# acb.net
KiCad netlist of a schematic drawn in EAGLE
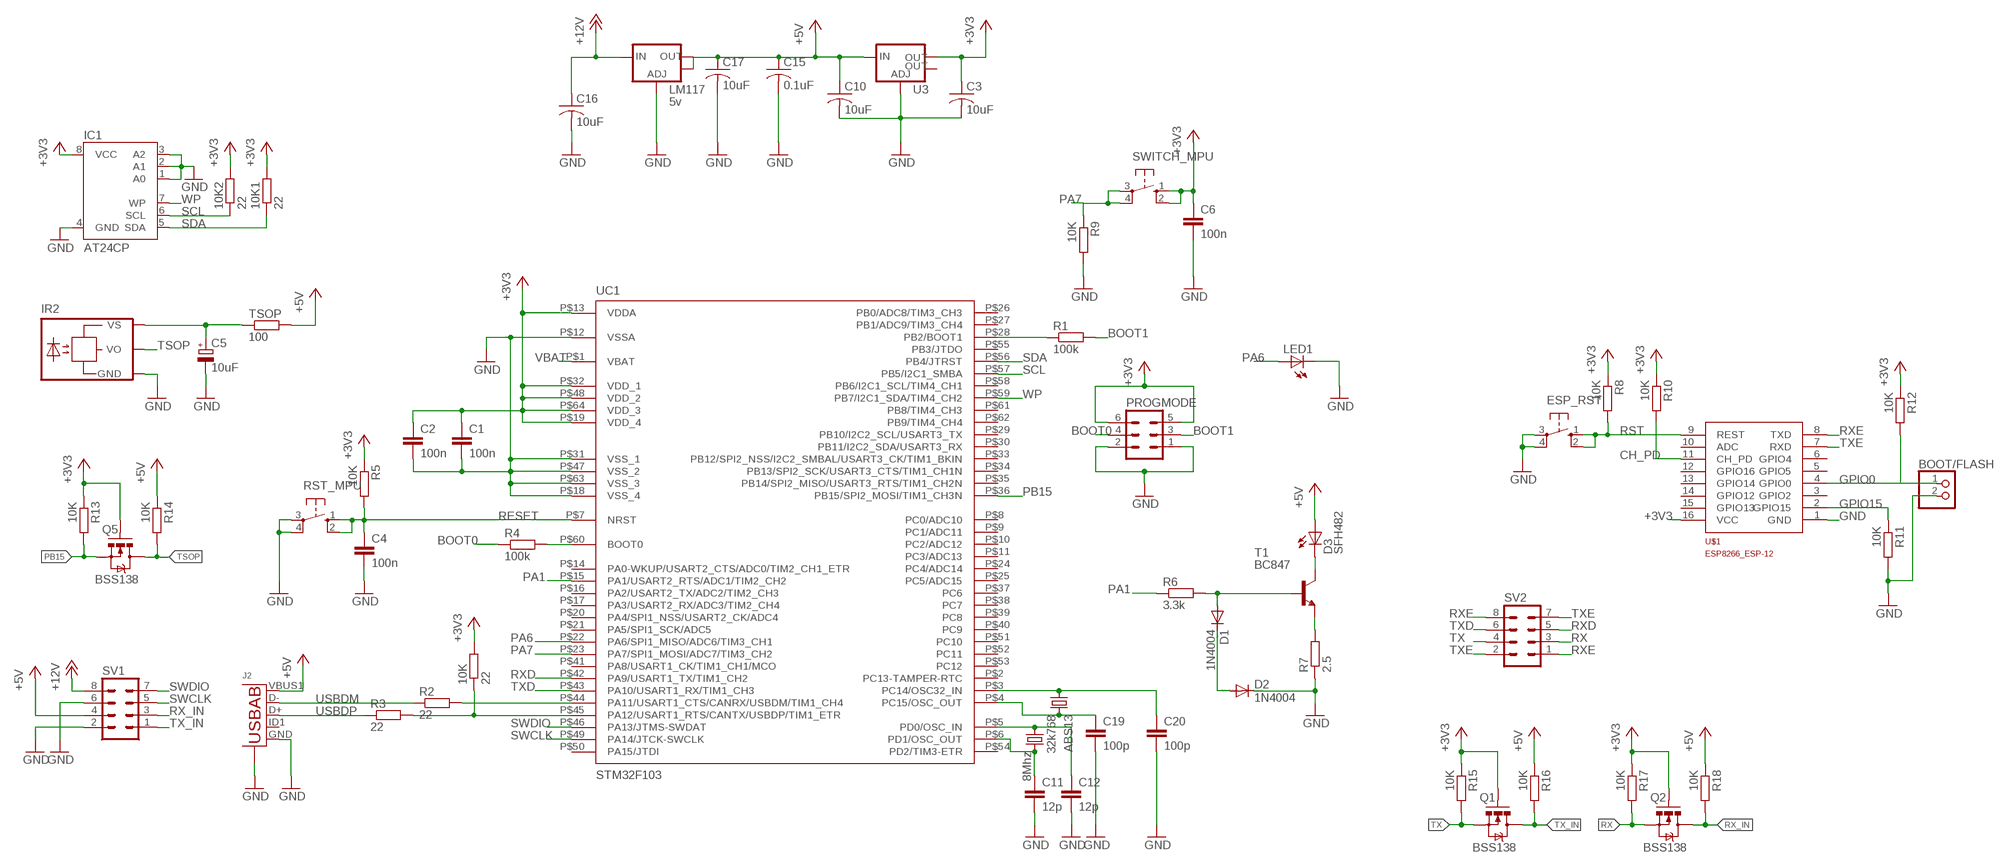
[diagram p0: schematic, sheet 1]

(export (version "E")
  (design (tool "Eeschema 10.0.6"))
  (components
    (comp (ref "10K")
      (value "22")
      (footprint "eagle-import:R1206")
      (libsource (lib "eagle-import") (part "R-EU_R1206"))
    )
    (comp (ref "10K1")
      (value "22")
      (footprint "eagle-import:R1206")
      (libsource (lib "eagle-import") (part "R-EU_R1206"))
    )
    (comp (ref "10K2")
      (value "22")
      (footprint "eagle-import:R1206")
      (libsource (lib "eagle-import") (part "R-EU_R1206"))
    )
    (comp (ref "ABS13")
      (value "32k768")
      (footprint "eagle-import:9HT7")
      (libsource (lib "eagle-import") (part "XTAL_9HT4"))
    )
    (comp (ref "BOOT/FLASH")
      (value "PINHD-1X2")
      (footprint "eagle-import:1X02")
      (libsource (lib "eagle-import") (part "PINHD-1X2"))
    )
    (comp (ref "C1")
      (value "100n")
      (footprint "eagle-import:C1206")
      (libsource (lib "eagle-import") (part "C-EUC1206"))
    )
    (comp (ref "C2")
      (value "100n")
      (footprint "eagle-import:C1206")
      (libsource (lib "eagle-import") (part "C-EUC1206"))
    )
    (comp (ref "C3")
      (value "10uF")
      (footprint "eagle-import:C1206")
      (libsource (lib "eagle-import") (part "C-USC1206"))
    )
    (comp (ref "C4")
      (value "100n")
      (footprint "eagle-import:C1206")
      (libsource (lib "eagle-import") (part "C-EUC1206"))
    )
    (comp (ref "C5")
      (value "10uF")
      (footprint "eagle-import:E2,5-6")
      (libsource (lib "eagle-import") (part "CPOL-EUE2.5-6"))
    )
    (comp (ref "C6")
      (value "100n")
      (footprint "eagle-import:C1206")
      (libsource (lib "eagle-import") (part "C-EUC1206"))
    )
    (comp (ref "C10")
      (value "10uF")
      (footprint "eagle-import:C1206")
      (libsource (lib "eagle-import") (part "C-USC1206"))
    )
    (comp (ref "C11")
      (value "12p")
      (footprint "eagle-import:C1206")
      (libsource (lib "eagle-import") (part "C-EUC1206"))
    )
    (comp (ref "C12")
      (value "12p")
      (footprint "eagle-import:C1206")
      (libsource (lib "eagle-import") (part "C-EUC1206"))
    )
    (comp (ref "C15")
      (value "0.1uF")
      (footprint "eagle-import:C0805")
      (libsource (lib "eagle-import") (part "resistor_C-USC0805"))
    )
    (comp (ref "C16")
      (value "10uF")
      (footprint "eagle-import:C0805")
      (libsource (lib "eagle-import") (part "resistor_C-USC0805"))
    )
    (comp (ref "C17")
      (value "10uF")
      (footprint "eagle-import:C0805")
      (libsource (lib "eagle-import") (part "resistor_C-USC0805"))
    )
    (comp (ref "C19")
      (value "100p")
      (footprint "eagle-import:C1206")
      (libsource (lib "eagle-import") (part "C-EUC1206"))
    )
    (comp (ref "C20")
      (value "100p")
      (footprint "eagle-import:C1206")
      (libsource (lib "eagle-import") (part "C-EUC1206"))
    )
    (comp (ref "D1")
      (value "1N4004")
      (footprint "eagle-import:DO41-10")
      (libsource (lib "eagle-import") (part "1N4004"))
    )
    (comp (ref "D2")
      (value "1N4004")
      (footprint "eagle-import:DO41-10")
      (libsource (lib "eagle-import") (part "1N4004"))
    )
    (comp (ref "D3")
      (value "SFH482")
      (footprint "eagle-import:SFH482")
      (libsource (lib "eagle-import") (part "SFH482"))
    )
    (comp (ref "ESP_RST")
      (value "10-XX")
      (footprint "eagle-import:B3F-10XX")
      (fields (field (name "MPN") "B3F-1000"))
      (libsource (lib "eagle-import") (part "10-XX"))
    )
    (comp (ref "IC1")
      (value "AT24CP")
      (footprint "eagle-import:DIL08")
      (fields (field (name "MPN") "AT24C1024BW-SH-B"))
      (libsource (lib "eagle-import") (part "AT24CP"))
    )
    (comp (ref "IR2")
      (value "TSOP1730TB1")
      (footprint "eagle-import:TSOP17_TB1")
      (libsource (lib "eagle-import") (part "TSOP17TB130"))
    )
    (comp (ref "J2")
      (value "USB-ABBG")
      (footprint "eagle-import:USB-AB-MICRO-SMD_V03_SF")
      (libsource (lib "eagle-import") (part "USB-ABBG"))
    )
    (comp (ref "LED1")
      (value "LED5MM")
      (footprint "eagle-import:LED5MM")
      (libsource (lib "eagle-import") (part "LED5MM"))
    )
    (comp (ref "LM117")
      (value "5v")
      (footprint "eagle-import:SOT223")
      (libsource (lib "eagle-import") (part "V_REG_LM1117SOT223"))
    )
    (comp (ref "PROGMODE")
      (value "MA03-2")
      (footprint "eagle-import:MA03-2")
      (libsource (lib "eagle-import") (part "MA03-2"))
    )
    (comp (ref "Q1")
      (value "BSS138")
      (footprint "eagle-import:SOT23-3")
      (libsource (lib "eagle-import") (part "MOSFET-NCHANNELSMD"))
    )
    (comp (ref "Q2")
      (value "BSS138")
      (footprint "eagle-import:SOT23-3")
      (libsource (lib "eagle-import") (part "MOSFET-NCHANNELSMD"))
    )
    (comp (ref "Q3")
      (value "8Mhz")
      (footprint "eagle-import:HC49U-V")
      (libsource (lib "eagle-import") (part "CRYSTALHC49U-V"))
    )
    (comp (ref "Q5")
      (value "BSS138")
      (footprint "eagle-import:SOT23-3")
      (libsource (lib "eagle-import") (part "MOSFET-NCHANNELSMD"))
    )
    (comp (ref "R1")
      (value "100k")
      (footprint "eagle-import:R1206")
      (libsource (lib "eagle-import") (part "R-EU_R1206"))
    )
    (comp (ref "R2")
      (value "22")
      (footprint "eagle-import:R1206")
      (libsource (lib "eagle-import") (part "R-EU_R1206"))
    )
    (comp (ref "R3")
      (value "22")
      (footprint "eagle-import:R1206")
      (libsource (lib "eagle-import") (part "R-EU_R1206"))
    )
    (comp (ref "R4")
      (value "100k")
      (footprint "eagle-import:R1206")
      (libsource (lib "eagle-import") (part "R-EU_R1206"))
    )
    (comp (ref "R5")
      (value "10K")
      (footprint "eagle-import:R1206")
      (libsource (lib "eagle-import") (part "R-EU_R1206"))
    )
    (comp (ref "R6")
      (value "3.3k")
      (footprint "eagle-import:R1206")
      (libsource (lib "eagle-import") (part "R-EU_R1206"))
    )
    (comp (ref "R7")
      (value "2.5")
      (footprint "eagle-import:R1206")
      (libsource (lib "eagle-import") (part "R-EU_R1206"))
    )
    (comp (ref "R8")
      (value "10K")
      (footprint "eagle-import:R1206")
      (libsource (lib "eagle-import") (part "R-EU_R1206"))
    )
    (comp (ref "R9")
      (value "10K")
      (footprint "eagle-import:R1206")
      (libsource (lib "eagle-import") (part "R-EU_R1206"))
    )
    (comp (ref "R10")
      (value "10K")
      (footprint "eagle-import:R1206")
      (libsource (lib "eagle-import") (part "R-EU_R1206"))
    )
    (comp (ref "R11")
      (value "10K")
      (footprint "eagle-import:R1206")
      (libsource (lib "eagle-import") (part "R-EU_R1206"))
    )
    (comp (ref "R12")
      (value "10K")
      (footprint "eagle-import:R1206")
      (libsource (lib "eagle-import") (part "R-EU_R1206"))
    )
    (comp (ref "R13")
      (value "10K")
      (footprint "eagle-import:R1206")
      (libsource (lib "eagle-import") (part "R-EU_R1206"))
    )
    (comp (ref "R14")
      (value "10K")
      (footprint "eagle-import:R1206")
      (libsource (lib "eagle-import") (part "R-EU_R1206"))
    )
    (comp (ref "R15")
      (value "10K")
      (footprint "eagle-import:R1206")
      (libsource (lib "eagle-import") (part "R-EU_R1206"))
    )
    (comp (ref "R16")
      (value "10K")
      (footprint "eagle-import:R1206")
      (libsource (lib "eagle-import") (part "R-EU_R1206"))
    )
    (comp (ref "R17")
      (value "10K")
      (footprint "eagle-import:R1206")
      (libsource (lib "eagle-import") (part "R-EU_R1206"))
    )
    (comp (ref "R18")
      (value "10K")
      (footprint "eagle-import:R1206")
      (libsource (lib "eagle-import") (part "R-EU_R1206"))
    )
    (comp (ref "RST_MPU")
      (value "10-XX")
      (footprint "eagle-import:B3F-10XX")
      (fields (field (name "MPN") "B3F-1000"))
      (libsource (lib "eagle-import") (part "10-XX"))
    )
    (comp (ref "SV1")
      (value "MA04-2")
      (footprint "eagle-import:MA04-2")
      (libsource (lib "eagle-import") (part "MA04-2"))
    )
    (comp (ref "SV2")
      (value "MA04-2")
      (footprint "eagle-import:MA04-2")
      (libsource (lib "eagle-import") (part "MA04-2"))
    )
    (comp (ref "SWITCH_MPU")
      (value "10-XX")
      (footprint "eagle-import:B3F-10XX")
      (fields (field (name "MPN") "B3F-1000"))
      (libsource (lib "eagle-import") (part "10-XX"))
    )
    (comp (ref "T1")
      (value "BC847")
      (footprint "eagle-import:SOT23")
      (libsource (lib "eagle-import") (part "BC847"))
    )
    (comp (ref "TSOP")
      (value "100")
      (footprint "eagle-import:R1206")
      (libsource (lib "eagle-import") (part "R-EU_R1206"))
    )
    (comp (ref "U$1")
      (value "ESP8266_ESP-12")
      (footprint "eagle-import:ESP8266-ESP12")
      (libsource (lib "eagle-import") (part "ESP8266_ESP-12"))
    )
    (comp (ref "U3")
      (value "V_REG_LM1117SOT223")
      (footprint "eagle-import:SOT223")
      (libsource (lib "eagle-import") (part "SparkFun-PowerIC_V_REG_LM1117SOT223"))
    )
    (comp (ref "UC1")
      (value "STM32F103")
      (footprint "eagle-import:TQFP-10X10-64")
      (libsource (lib "eagle-import") (part "STM32F103"))
    )
  )
  (nets
    (net (code "1") (name "+3V3") (class "Default")
      (node (ref "10K") (pin "2") (pinfunction "2_2") (pintype "passive"))
      (node (ref "10K1") (pin "2") (pinfunction "2_2") (pintype "passive"))
      (node (ref "10K2") (pin "2") (pinfunction "2_2") (pintype "passive"))
      (node (ref "C1") (pin "1") (pinfunction "1_1") (pintype "passive"))
      (node (ref "C2") (pin "1") (pinfunction "1_1") (pintype "passive"))
      (node (ref "C3") (pin "1") (pinfunction "1_1") (pintype "passive"))
      (node (ref "C6") (pin "1") (pinfunction "1_1") (pintype "passive"))
      (node (ref "IC1") (pin "8") (pinfunction "VCC_8") (pintype "power_in"))
      (node (ref "PROGMODE") (pin "5") (pinfunction "5_5") (pintype "passive"))
      (node (ref "PROGMODE") (pin "6") (pinfunction "6_6") (pintype "passive"))
      (node (ref "Q1") (pin "1") (pinfunction "G_1") (pintype "passive"))
      (node (ref "Q2") (pin "1") (pinfunction "G_1") (pintype "passive"))
      (node (ref "Q5") (pin "1") (pinfunction "G_1") (pintype "passive"))
      (node (ref "R10") (pin "1") (pinfunction "1_1") (pintype "passive"))
      (node (ref "R12") (pin "1") (pinfunction "1_1") (pintype "passive"))
      (node (ref "R13") (pin "1") (pinfunction "1_1") (pintype "passive"))
      (node (ref "R15") (pin "1") (pinfunction "1_1") (pintype "passive"))
      (node (ref "R17") (pin "1") (pinfunction "1_1") (pintype "passive"))
      (node (ref "R5") (pin "1") (pinfunction "1_1") (pintype "passive"))
      (node (ref "R8") (pin "1") (pinfunction "1_1") (pintype "passive"))
      (node (ref "SWITCH_MPU") (pin "1") (pinfunction "S_1") (pintype "passive"))
      (node (ref "SWITCH_MPU") (pin "2") (pinfunction "S1_2") (pintype "passive"))
      (node (ref "U$1") (pin "16") (pinfunction "VCC_16") (pintype "bidirectional"))
      (node (ref "U3") (pin "2") (pinfunction "OUT_2") (pintype "output"))
      (node (ref "UC1") (pin "P$13") (pinfunction "VDDA_P$13") (pintype "power_in"))
      (node (ref "UC1") (pin "P$19") (pinfunction "VDD_4_P$19") (pintype "power_in"))
      (node (ref "UC1") (pin "P$32") (pinfunction "VDD_1_P$32") (pintype "power_in"))
      (node (ref "UC1") (pin "P$48") (pinfunction "VDD_2_P$48") (pintype "power_in"))
      (node (ref "UC1") (pin "P$64") (pinfunction "VDD_3_P$64") (pintype "power_in"))
    )
    (net (code "2") (name "+5V") (class "Default")
      (node (ref "C10") (pin "1") (pinfunction "1_1") (pintype "passive"))
      (node (ref "C15") (pin "1") (pinfunction "1_1") (pintype "passive"))
      (node (ref "C17") (pin "1") (pinfunction "1_1") (pintype "passive"))
      (node (ref "D3") (pin "A") (pinfunction "A_A") (pintype "passive"))
      (node (ref "J2") (pin "VBUS1") (pinfunction "VBUS_VBUS1") (pintype "bidirectional"))
      (node (ref "LM117") (pin "2") (pinfunction "OUT_2") (pintype "output"))
      (node (ref "LM117") (pin "4") (pinfunction "OUT_4") (pintype "output"))
      (node (ref "R14") (pin "1") (pinfunction "1_1") (pintype "passive"))
      (node (ref "R16") (pin "1") (pinfunction "1_1") (pintype "passive"))
      (node (ref "R18") (pin "1") (pinfunction "1_1") (pintype "passive"))
      (node (ref "SV1") (pin "4") (pinfunction "4_4") (pintype "passive"))
      (node (ref "TSOP") (pin "2") (pinfunction "2_2") (pintype "passive"))
      (node (ref "U3") (pin "3") (pinfunction "IN_3") (pintype "input"))
    )
    (net (code "3") (name "+12V") (class "Default")
      (node (ref "C16") (pin "1") (pinfunction "1_1") (pintype "passive"))
      (node (ref "LM117") (pin "3") (pinfunction "IN_3") (pintype "input"))
      (node (ref "SV1") (pin "8") (pinfunction "8_8") (pintype "passive"))
    )
    (net (code "4") (name "/BOOT0") (class "Default")
      (node (ref "PROGMODE") (pin "4") (pinfunction "4_4") (pintype "passive"))
      (node (ref "R4") (pin "1") (pinfunction "1_1") (pintype "passive"))
    )
    (net (code "5") (name "/BOOT1") (class "Default")
      (node (ref "PROGMODE") (pin "3") (pinfunction "3_3") (pintype "passive"))
      (node (ref "R1") (pin "2") (pinfunction "2_2") (pintype "passive"))
    )
    (net (code "6") (name "/CH_PD") (class "Default")
      (node (ref "R10") (pin "2") (pinfunction "2_2") (pintype "passive"))
      (node (ref "U$1") (pin "11") (pinfunction "CH_PD_11") (pintype "bidirectional"))
    )
    (net (code "7") (name "/GPIO0") (class "Default")
      (node (ref "BOOT/FLASH") (pin "1") (pinfunction "1_1") (pintype "passive"))
      (node (ref "R12") (pin "2") (pinfunction "2_2") (pintype "passive"))
      (node (ref "U$1") (pin "4") (pinfunction "GPIO0_4") (pintype "bidirectional"))
    )
    (net (code "8") (name "/GPIO15") (class "Default")
      (node (ref "R11") (pin "1") (pinfunction "1_1") (pintype "passive"))
      (node (ref "U$1") (pin "2") (pinfunction "GPIO15_2") (pintype "bidirectional"))
    )
    (net (code "9") (name "/PA1") (class "Default")
      (node (ref "R6") (pin "1") (pinfunction "1_1") (pintype "passive"))
      (node (ref "UC1") (pin "P$15") (pinfunction "PA1/USART2_RTS/ADC1/TIM2_CH2_P$15") (pintype "bidirectional"))
    )
    (net (code "10") (name "/PA6") (class "Default")
      (node (ref "LED1") (pin "A") (pinfunction "A_A") (pintype "passive"))
      (node (ref "UC1") (pin "P$22") (pinfunction "PA6/SPI1_MISO/ADC6/TIM3_CH1_P$22") (pintype "bidirectional"))
    )
    (net (code "11") (name "/PA7") (class "Default")
      (node (ref "R9") (pin "1") (pinfunction "1_1") (pintype "passive"))
      (node (ref "SWITCH_MPU") (pin "3") (pinfunction "P_3") (pintype "passive"))
      (node (ref "SWITCH_MPU") (pin "4") (pinfunction "P1_4") (pintype "passive"))
      (node (ref "UC1") (pin "P$23") (pinfunction "PA7/SPI1_MOSI/ADC7/TIM3_CH2_P$23") (pintype "bidirectional"))
    )
    (net (code "12") (name "/RESET") (class "Default")
      (node (ref "C4") (pin "1") (pinfunction "1_1") (pintype "passive"))
      (node (ref "R5") (pin "2") (pinfunction "2_2") (pintype "passive"))
      (node (ref "RST_MPU") (pin "1") (pinfunction "S_1") (pintype "passive"))
      (node (ref "RST_MPU") (pin "2") (pinfunction "S1_2") (pintype "passive"))
      (node (ref "UC1") (pin "P$7") (pinfunction "NRST_P$7") (pintype "bidirectional"))
    )
    (net (code "13") (name "/RST") (class "Default")
      (node (ref "ESP_RST") (pin "1") (pinfunction "S_1") (pintype "passive"))
      (node (ref "ESP_RST") (pin "2") (pinfunction "S1_2") (pintype "passive"))
      (node (ref "R8") (pin "2") (pinfunction "2_2") (pintype "passive"))
      (node (ref "U$1") (pin "9") (pinfunction "REST_9") (pintype "bidirectional"))
    )
    (net (code "14") (name "/RXD") (class "Default")
      (node (ref "SV2") (pin "5") (pinfunction "5_5") (pintype "passive"))
      (node (ref "UC1") (pin "P$42") (pinfunction "PA9/USART1_TX/TIM1_CH2_P$42") (pintype "bidirectional"))
    )
    (net (code "15") (name "/RXE") (class "Default")
      (node (ref "SV2") (pin "1") (pinfunction "1_1") (pintype "passive"))
      (node (ref "SV2") (pin "8") (pinfunction "8_8") (pintype "passive"))
      (node (ref "U$1") (pin "8") (pinfunction "TXD_8") (pintype "bidirectional"))
    )
    (net (code "16") (name "/SCL") (class "Default")
      (node (ref "10K2") (pin "1") (pinfunction "1_1") (pintype "passive"))
      (node (ref "IC1") (pin "6") (pinfunction "SCL_6") (pintype "bidirectional"))
      (node (ref "UC1") (pin "P$57") (pinfunction "PB5/I2C1_SMBA_P$57") (pintype "bidirectional"))
    )
    (net (code "17") (name "/SDA") (class "Default")
      (node (ref "10K1") (pin "1") (pinfunction "1_1") (pintype "passive"))
      (node (ref "IC1") (pin "5") (pinfunction "SDA_5") (pintype "bidirectional"))
      (node (ref "UC1") (pin "P$56") (pinfunction "PB4/JTRST_P$56") (pintype "bidirectional"))
    )
    (net (code "18") (name "/SWCLK") (class "Default")
      (node (ref "SV1") (pin "5") (pinfunction "5_5") (pintype "passive"))
      (node (ref "UC1") (pin "P$49") (pinfunction "PA14/JTCK-SWCLK_P$49") (pintype "bidirectional"))
    )
    (net (code "19") (name "/SWDIO") (class "Default")
      (node (ref "SV1") (pin "7") (pinfunction "7_7") (pintype "passive"))
      (node (ref "UC1") (pin "P$46") (pinfunction "PA13/JTMS-SWDAT_P$46") (pintype "bidirectional"))
    )
    (net (code "20") (name "/TXD") (class "Default")
      (node (ref "SV2") (pin "6") (pinfunction "6_6") (pintype "passive"))
      (node (ref "UC1") (pin "P$43") (pinfunction "PA10/USART1_RX/TIM1_CH3_P$43") (pintype "bidirectional"))
    )
    (net (code "21") (name "/TXE") (class "Default")
      (node (ref "SV2") (pin "2") (pinfunction "2_2") (pintype "passive"))
      (node (ref "SV2") (pin "7") (pinfunction "7_7") (pintype "passive"))
      (node (ref "U$1") (pin "7") (pinfunction "RXD_7") (pintype "bidirectional"))
    )
    (net (code "22") (name "/USBDM") (class "Default")
      (node (ref "J2") (pin "D-") (pinfunction "D-_D-") (pintype "bidirectional"))
      (node (ref "R2") (pin "1") (pinfunction "1_1") (pintype "passive"))
    )
    (net (code "23") (name "/USBDP") (class "Default")
      (node (ref "J2") (pin "D+") (pinfunction "D+_D+") (pintype "bidirectional"))
      (node (ref "R3") (pin "1") (pinfunction "1_1") (pintype "passive"))
    )
    (net (code "24") (name "/VBAT") (class "Default")
      (node (ref "UC1") (pin "P$1") (pinfunction "VBAT_P$1") (pintype "power_in"))
    )
    (net (code "25") (name "/WP") (class "Default")
      (node (ref "IC1") (pin "7") (pinfunction "WP_7") (pintype "input"))
      (node (ref "UC1") (pin "P$59") (pinfunction "PB7/I2C1_SDA/TIM4_CH2_P$59") (pintype "bidirectional"))
    )
    (net (code "26") (name "GND") (class "Default")
      (node (ref "BOOT/FLASH") (pin "2") (pinfunction "2_2") (pintype "passive"))
      (node (ref "C1") (pin "2") (pinfunction "2_2") (pintype "passive"))
      (node (ref "C10") (pin "2") (pinfunction "2_2") (pintype "passive"))
      (node (ref "C11") (pin "2") (pinfunction "2_2") (pintype "passive"))
      (node (ref "C12") (pin "2") (pinfunction "2_2") (pintype "passive"))
      (node (ref "C15") (pin "2") (pinfunction "2_2") (pintype "passive"))
      (node (ref "C16") (pin "2") (pinfunction "2_2") (pintype "passive"))
      (node (ref "C17") (pin "2") (pinfunction "2_2") (pintype "passive"))
      (node (ref "C19") (pin "2") (pinfunction "2_2") (pintype "passive"))
      (node (ref "C2") (pin "2") (pinfunction "2_2") (pintype "passive"))
      (node (ref "C20") (pin "2") (pinfunction "2_2") (pintype "passive"))
      (node (ref "C3") (pin "2") (pinfunction "2_2") (pintype "passive"))
      (node (ref "C4") (pin "2") (pinfunction "2_2") (pintype "passive"))
      (node (ref "C5") (pin "-") (pinfunction "-_-") (pintype "passive"))
      (node (ref "C6") (pin "2") (pinfunction "2_2") (pintype "passive"))
      (node (ref "D2") (pin "C") (pinfunction "C_C") (pintype "passive"))
      (node (ref "ESP_RST") (pin "3") (pinfunction "P_3") (pintype "passive"))
      (node (ref "ESP_RST") (pin "4") (pinfunction "P1_4") (pintype "passive"))
      (node (ref "IC1") (pin "1") (pinfunction "A0_1") (pintype "input"))
      (node (ref "IC1") (pin "2") (pinfunction "A1_2") (pintype "input"))
      (node (ref "IC1") (pin "3") (pinfunction "A2_3") (pintype "input"))
      (node (ref "IC1") (pin "4") (pinfunction "GND_4") (pintype "power_in"))
      (node (ref "IR2") (pin "GND") (pinfunction "GND_GND") (pintype "power_in"))
      (node (ref "J2") (pin "GND") (pinfunction "GND_GND") (pintype "bidirectional"))
      (node (ref "J2") (pin "S1") (pinfunction "S_S1") (pintype "bidirectional"))
      (node (ref "J2") (pin "S2") (pinfunction "S_S2") (pintype "bidirectional"))
      (node (ref "J2") (pin "S3") (pinfunction "S_S3") (pintype "bidirectional"))
      (node (ref "J2") (pin "S4") (pinfunction "S_S4") (pintype "bidirectional"))
      (node (ref "LED1") (pin "K") (pinfunction "C_K") (pintype "passive"))
      (node (ref "LM117") (pin "1") (pinfunction "ADJ_1") (pintype "input"))
      (node (ref "PROGMODE") (pin "1") (pinfunction "1_1") (pintype "passive"))
      (node (ref "PROGMODE") (pin "2") (pinfunction "2_2") (pintype "passive"))
      (node (ref "R11") (pin "2") (pinfunction "2_2") (pintype "passive"))
      (node (ref "R7") (pin "1") (pinfunction "1_1") (pintype "passive"))
      (node (ref "R9") (pin "2") (pinfunction "2_2") (pintype "passive"))
      (node (ref "RST_MPU") (pin "3") (pinfunction "P_3") (pintype "passive"))
      (node (ref "RST_MPU") (pin "4") (pinfunction "P1_4") (pintype "passive"))
      (node (ref "SV1") (pin "2") (pinfunction "2_2") (pintype "passive"))
      (node (ref "SV1") (pin "6") (pinfunction "6_6") (pintype "passive"))
      (node (ref "U$1") (pin "1") (pinfunction "GND_1") (pintype "bidirectional"))
      (node (ref "U3") (pin "1") (pinfunction "ADJ_1") (pintype "input"))
      (node (ref "UC1") (pin "P$12") (pinfunction "VSSA_P$12") (pintype "power_in"))
      (node (ref "UC1") (pin "P$18") (pinfunction "VSS_4_P$18") (pintype "power_in"))
      (node (ref "UC1") (pin "P$31") (pinfunction "VSS_1_P$31") (pintype "power_in"))
      (node (ref "UC1") (pin "P$47") (pinfunction "VSS_2_P$47") (pintype "power_in"))
      (node (ref "UC1") (pin "P$63") (pinfunction "VSS_3_P$63") (pintype "power_in"))
    )
    (net (code "27") (name "Net-(ABS13-2)") (class "Default")
      (node (ref "ABS13") (pin "4") (pinfunction "2_4") (pintype "passive"))
      (node (ref "C19") (pin "1") (pinfunction "1_1") (pintype "passive"))
      (node (ref "UC1") (pin "P$4") (pinfunction "PC15/OSC_OUT_P$4") (pintype "bidirectional"))
    )
    (net (code "28") (name "Net-(C5-Pad+)") (class "Default")
      (node (ref "C5") (pin "+") (pinfunction "+_+") (pintype "passive"))
      (node (ref "IR2") (pin "VS") (pinfunction "VS_VS") (pintype "power_in"))
      (node (ref "TSOP") (pin "1") (pinfunction "1_1") (pintype "passive"))
    )
    (net (code "29") (name "Net-(D1-PadC)") (class "Default")
      (node (ref "D1") (pin "C") (pinfunction "C_C") (pintype "passive"))
      (node (ref "D2") (pin "A") (pinfunction "A_A") (pintype "passive"))
    )
    (net (code "30") (name "Net-(D3-C)") (class "Default")
      (node (ref "D3") (pin "K") (pinfunction "C_K") (pintype "passive"))
      (node (ref "T1") (pin "3") (pinfunction "C_3") (pintype "passive"))
    )
    (net (code "31") (name "Net-(T1-B)") (class "Default")
      (node (ref "D1") (pin "A") (pinfunction "A_A") (pintype "passive"))
      (node (ref "R6") (pin "2") (pinfunction "2_2") (pintype "passive"))
      (node (ref "T1") (pin "1") (pinfunction "B_1") (pintype "passive"))
    )
    (net (code "32") (name "Net-(T1-E)") (class "Default")
      (node (ref "R7") (pin "2") (pinfunction "2_2") (pintype "passive"))
      (node (ref "T1") (pin "2") (pinfunction "E_2") (pintype "passive"))
    )
    (net (code "33") (name "Net-(UC1-BOOT0)") (class "Default")
      (node (ref "R4") (pin "2") (pinfunction "2_2") (pintype "passive"))
      (node (ref "UC1") (pin "P$60") (pinfunction "BOOT0_P$60") (pintype "bidirectional"))
    )
    (net (code "34") (name "Net-(UC1-PA11{slash}USART1_CTS{slash}CANRX{slash}USBDM{slash}TIM1_CH4)") (class "Default")
      (node (ref "R2") (pin "2") (pinfunction "2_2") (pintype "passive"))
      (node (ref "UC1") (pin "P$44") (pinfunction "PA11/USART1_CTS/CANRX/USBDM/TIM1_CH4_P$44") (pintype "bidirectional"))
    )
    (net (code "35") (name "Net-(UC1-PA12{slash}USART1_RTS{slash}CANTX{slash}USBDP{slash}TIM1_ETR)") (class "Default")
      (node (ref "10K") (pin "1") (pinfunction "1_1") (pintype "passive"))
      (node (ref "R3") (pin "2") (pinfunction "2_2") (pintype "passive"))
      (node (ref "UC1") (pin "P$45") (pinfunction "PA12/USART1_RTS/CANTX/USBDP/TIM1_ETR_P$45") (pintype "bidirectional"))
    )
    (net (code "36") (name "Net-(UC1-PB2{slash}BOOT1)") (class "Default")
      (node (ref "R1") (pin "1") (pinfunction "1_1") (pintype "passive"))
      (node (ref "UC1") (pin "P$28") (pinfunction "PB2/BOOT1_P$28") (pintype "bidirectional"))
    )
    (net (code "37") (name "Net-(UC1-PC14{slash}OSC32_IN)") (class "Default")
      (node (ref "ABS13") (pin "1") (pinfunction "1_1") (pintype "passive"))
      (node (ref "C20") (pin "1") (pinfunction "1_1") (pintype "passive"))
      (node (ref "UC1") (pin "P$3") (pinfunction "PC14/OSC32_IN_P$3") (pintype "bidirectional"))
    )
    (net (code "38") (name "Net-(UC1-PD0{slash}OSC_IN)") (class "Default")
      (node (ref "C12") (pin "1") (pinfunction "1_1") (pintype "passive"))
      (node (ref "Q3") (pin "1") (pinfunction "1_1") (pintype "passive"))
      (node (ref "UC1") (pin "P$5") (pinfunction "PD0/OSC_IN_P$5") (pintype "bidirectional"))
    )
    (net (code "39") (name "Net-(UC1-PD1{slash}OSC_OUT)") (class "Default")
      (node (ref "C11") (pin "1") (pinfunction "1_1") (pintype "passive"))
      (node (ref "Q3") (pin "2") (pinfunction "2_2") (pintype "passive"))
      (node (ref "UC1") (pin "P$6") (pinfunction "PD1/OSC_OUT_P$6") (pintype "bidirectional"))
    )
    (net (code "40") (name "PB15") (class "Default")
      (node (ref "Q5") (pin "2") (pinfunction "S_2") (pintype "passive"))
      (node (ref "R13") (pin "2") (pinfunction "2_2") (pintype "passive"))
      (node (ref "UC1") (pin "P$36") (pinfunction "PB15/SPI2_MOSI/TIM1_CH3N_P$36") (pintype "bidirectional"))
    )
    (net (code "41") (name "RX") (class "Default")
      (node (ref "Q2") (pin "2") (pinfunction "S_2") (pintype "passive"))
      (node (ref "R17") (pin "2") (pinfunction "2_2") (pintype "passive"))
      (node (ref "SV2") (pin "3") (pinfunction "3_3") (pintype "passive"))
    )
    (net (code "42") (name "RX_IN") (class "Default")
      (node (ref "Q2") (pin "3") (pinfunction "D_3") (pintype "passive"))
      (node (ref "R18") (pin "2") (pinfunction "2_2") (pintype "passive"))
      (node (ref "SV1") (pin "3") (pinfunction "3_3") (pintype "passive"))
    )
    (net (code "43") (name "TSOP") (class "Default")
      (node (ref "IR2") (pin "VO") (pinfunction "VO_VO") (pintype "open_collector"))
      (node (ref "Q5") (pin "3") (pinfunction "D_3") (pintype "passive"))
      (node (ref "R14") (pin "2") (pinfunction "2_2") (pintype "passive"))
    )
    (net (code "44") (name "TX") (class "Default")
      (node (ref "Q1") (pin "2") (pinfunction "S_2") (pintype "passive"))
      (node (ref "R15") (pin "2") (pinfunction "2_2") (pintype "passive"))
      (node (ref "SV2") (pin "4") (pinfunction "4_4") (pintype "passive"))
    )
    (net (code "45") (name "TX_IN") (class "Default")
      (node (ref "Q1") (pin "3") (pinfunction "D_3") (pintype "passive"))
      (node (ref "R16") (pin "2") (pinfunction "2_2") (pintype "passive"))
      (node (ref "SV1") (pin "1") (pinfunction "1_1") (pintype "passive"))
    )
    (net (code "46") (name "unconnected-(J2-USBID-PadID1)") (class "Default")
      (node (ref "J2") (pin "ID1") (pinfunction "USBID_ID1") (pintype "bidirectional"))
    )
    (net (code "47") (name "unconnected-(U$1-ADC-Pad10)") (class "Default")
      (node (ref "U$1") (pin "10") (pinfunction "ADC_10") (pintype "bidirectional"))
    )
    (net (code "48") (name "unconnected-(U$1-GPIO2-Pad3)") (class "Default")
      (node (ref "U$1") (pin "3") (pinfunction "GPIO2_3") (pintype "bidirectional"))
    )
    (net (code "49") (name "unconnected-(U$1-GPIO4-Pad6)") (class "Default")
      (node (ref "U$1") (pin "6") (pinfunction "GPIO4_6") (pintype "bidirectional"))
    )
    (net (code "50") (name "unconnected-(U$1-GPIO5-Pad5)") (class "Default")
      (node (ref "U$1") (pin "5") (pinfunction "GPIO5_5") (pintype "bidirectional"))
    )
    (net (code "51") (name "unconnected-(U$1-GPIO12-Pad14)") (class "Default")
      (node (ref "U$1") (pin "14") (pinfunction "GPIO12_14") (pintype "bidirectional"))
    )
    (net (code "52") (name "unconnected-(U$1-GPIO13-Pad15)") (class "Default")
      (node (ref "U$1") (pin "15") (pinfunction "GPIO13_15") (pintype "bidirectional"))
    )
    (net (code "53") (name "unconnected-(U$1-GPIO14-Pad13)") (class "Default")
      (node (ref "U$1") (pin "13") (pinfunction "GPIO14_13") (pintype "bidirectional"))
    )
    (net (code "54") (name "unconnected-(U$1-GPIO16-Pad12)") (class "Default")
      (node (ref "U$1") (pin "12") (pinfunction "GPIO16_12") (pintype "bidirectional"))
    )
    (net (code "55") (name "unconnected-(U3-OUT-Pad4)") (class "Default")
      (node (ref "U3") (pin "4") (pinfunction "OUT_4") (pintype "output"))
    )
    (net (code "56") (name "unconnected-(UC1-PA0-WKUP{slash}USART2_CTS{slash}ADC0{slash}TIM2_CH1_ETR-PadP$14)") (class "Default")
      (node (ref "UC1") (pin "P$14") (pinfunction "PA0-WKUP/USART2_CTS/ADC0/TIM2_CH1_ETR_P$14") (pintype "bidirectional"))
    )
    (net (code "57") (name "unconnected-(UC1-PA2{slash}USART2_TX{slash}ADC2{slash}TIM2_CH3-PadP$16)") (class "Default")
      (node (ref "UC1") (pin "P$16") (pinfunction "PA2/USART2_TX/ADC2/TIM2_CH3_P$16") (pintype "bidirectional"))
    )
    (net (code "58") (name "unconnected-(UC1-PA3{slash}USART2_RX{slash}ADC3{slash}TIM2_CH4-PadP$17)") (class "Default")
      (node (ref "UC1") (pin "P$17") (pinfunction "PA3/USART2_RX/ADC3/TIM2_CH4_P$17") (pintype "bidirectional"))
    )
    (net (code "59") (name "unconnected-(UC1-PA4{slash}SPI1_NSS{slash}USART2_CK{slash}ADC4-PadP$20)") (class "Default")
      (node (ref "UC1") (pin "P$20") (pinfunction "PA4/SPI1_NSS/USART2_CK/ADC4_P$20") (pintype "bidirectional"))
    )
    (net (code "60") (name "unconnected-(UC1-PA5{slash}SPI1_SCK{slash}ADC5-PadP$21)") (class "Default")
      (node (ref "UC1") (pin "P$21") (pinfunction "PA5/SPI1_SCK/ADC5_P$21") (pintype "bidirectional"))
    )
    (net (code "61") (name "unconnected-(UC1-PA8{slash}USART1_CK{slash}TIM1_CH1{slash}MCO-PadP$41)") (class "Default")
      (node (ref "UC1") (pin "P$41") (pinfunction "PA8/USART1_CK/TIM1_CH1/MCO_P$41") (pintype "bidirectional"))
    )
    (net (code "62") (name "unconnected-(UC1-PA15{slash}JTDI-PadP$50)") (class "Default")
      (node (ref "UC1") (pin "P$50") (pinfunction "PA15/JTDI_P$50") (pintype "bidirectional"))
    )
    (net (code "63") (name "unconnected-(UC1-PB0{slash}ADC8{slash}TIM3_CH3-PadP$26)") (class "Default")
      (node (ref "UC1") (pin "P$26") (pinfunction "PB0/ADC8/TIM3_CH3_P$26") (pintype "bidirectional"))
    )
    (net (code "64") (name "unconnected-(UC1-PB1{slash}ADC9{slash}TIM3_CH4-PadP$27)") (class "Default")
      (node (ref "UC1") (pin "P$27") (pinfunction "PB1/ADC9/TIM3_CH4_P$27") (pintype "bidirectional"))
    )
    (net (code "65") (name "unconnected-(UC1-PB3{slash}JTDO-PadP$55)") (class "Default")
      (node (ref "UC1") (pin "P$55") (pinfunction "PB3/JTDO_P$55") (pintype "bidirectional"))
    )
    (net (code "66") (name "unconnected-(UC1-PB6{slash}I2C1_SCL{slash}TIM4_CH1-PadP$58)") (class "Default")
      (node (ref "UC1") (pin "P$58") (pinfunction "PB6/I2C1_SCL/TIM4_CH1_P$58") (pintype "bidirectional"))
    )
    (net (code "67") (name "unconnected-(UC1-PB8{slash}TIM4_CH3-PadP$61)") (class "Default")
      (node (ref "UC1") (pin "P$61") (pinfunction "PB8/TIM4_CH3_P$61") (pintype "bidirectional"))
    )
    (net (code "68") (name "unconnected-(UC1-PB9{slash}TIM4_CH4-PadP$62)") (class "Default")
      (node (ref "UC1") (pin "P$62") (pinfunction "PB9/TIM4_CH4_P$62") (pintype "bidirectional"))
    )
    (net (code "69") (name "unconnected-(UC1-PB10{slash}I2C2_SCL{slash}USART3_TX-PadP$29)") (class "Default")
      (node (ref "UC1") (pin "P$29") (pinfunction "PB10/I2C2_SCL/USART3_TX_P$29") (pintype "bidirectional"))
    )
    (net (code "70") (name "unconnected-(UC1-PB11{slash}I2C2_SDA{slash}USART3_RX-PadP$30)") (class "Default")
      (node (ref "UC1") (pin "P$30") (pinfunction "PB11/I2C2_SDA/USART3_RX_P$30") (pintype "bidirectional"))
    )
    (net (code "71") (name "unconnected-(UC1-PB12{slash}SPI2_NSS{slash}I2C2_SMBAL{slash}USART3_CK{slash}TIM1_BKIN-PadP$33)") (class "Default")
      (node (ref "UC1") (pin "P$33") (pinfunction "PB12/SPI2_NSS/I2C2_SMBAL/USART3_CK/TIM1_BKIN_P$33") (pintype "bidirectional"))
    )
    (net (code "72") (name "unconnected-(UC1-PB13{slash}SPI2_SCK{slash}USART3_CTS{slash}TIM1_CH1N-PadP$34)") (class "Default")
      (node (ref "UC1") (pin "P$34") (pinfunction "PB13/SPI2_SCK/USART3_CTS/TIM1_CH1N_P$34") (pintype "bidirectional"))
    )
    (net (code "73") (name "unconnected-(UC1-PB14{slash}SPI2_MISO{slash}USART3_RTS{slash}TIM1_CH2N-PadP$35)") (class "Default")
      (node (ref "UC1") (pin "P$35") (pinfunction "PB14/SPI2_MISO/USART3_RTS/TIM1_CH2N_P$35") (pintype "bidirectional"))
    )
    (net (code "74") (name "unconnected-(UC1-PC0{slash}ADC10-PadP$8)") (class "Default")
      (node (ref "UC1") (pin "P$8") (pinfunction "PC0/ADC10_P$8") (pintype "bidirectional"))
    )
    (net (code "75") (name "unconnected-(UC1-PC1{slash}ADC11-PadP$9)") (class "Default")
      (node (ref "UC1") (pin "P$9") (pinfunction "PC1/ADC11_P$9") (pintype "bidirectional"))
    )
    (net (code "76") (name "unconnected-(UC1-PC2{slash}ADC12-PadP$10)") (class "Default")
      (node (ref "UC1") (pin "P$10") (pinfunction "PC2/ADC12_P$10") (pintype "bidirectional"))
    )
    (net (code "77") (name "unconnected-(UC1-PC3{slash}ADC13-PadP$11)") (class "Default")
      (node (ref "UC1") (pin "P$11") (pinfunction "PC3/ADC13_P$11") (pintype "bidirectional"))
    )
    (net (code "78") (name "unconnected-(UC1-PC4{slash}ADC14-PadP$24)") (class "Default")
      (node (ref "UC1") (pin "P$24") (pinfunction "PC4/ADC14_P$24") (pintype "bidirectional"))
    )
    (net (code "79") (name "unconnected-(UC1-PC5{slash}ADC15-PadP$25)") (class "Default")
      (node (ref "UC1") (pin "P$25") (pinfunction "PC5/ADC15_P$25") (pintype "bidirectional"))
    )
    (net (code "80") (name "unconnected-(UC1-PC6-PadP$37)") (class "Default")
      (node (ref "UC1") (pin "P$37") (pinfunction "PC6_P$37") (pintype "bidirectional"))
    )
    (net (code "81") (name "unconnected-(UC1-PC7-PadP$38)") (class "Default")
      (node (ref "UC1") (pin "P$38") (pinfunction "PC7_P$38") (pintype "bidirectional"))
    )
    (net (code "82") (name "unconnected-(UC1-PC8-PadP$39)") (class "Default")
      (node (ref "UC1") (pin "P$39") (pinfunction "PC8_P$39") (pintype "bidirectional"))
    )
    (net (code "83") (name "unconnected-(UC1-PC9-PadP$40)") (class "Default")
      (node (ref "UC1") (pin "P$40") (pinfunction "PC9_P$40") (pintype "bidirectional"))
    )
    (net (code "84") (name "unconnected-(UC1-PC10-PadP$51)") (class "Default")
      (node (ref "UC1") (pin "P$51") (pinfunction "PC10_P$51") (pintype "bidirectional"))
    )
    (net (code "85") (name "unconnected-(UC1-PC11-PadP$52)") (class "Default")
      (node (ref "UC1") (pin "P$52") (pinfunction "PC11_P$52") (pintype "bidirectional"))
    )
    (net (code "86") (name "unconnected-(UC1-PC12-PadP$53)") (class "Default")
      (node (ref "UC1") (pin "P$53") (pinfunction "PC12_P$53") (pintype "bidirectional"))
    )
    (net (code "87") (name "unconnected-(UC1-PC13-TAMPER-RTC-PadP$2)") (class "Default")
      (node (ref "UC1") (pin "P$2") (pinfunction "PC13-TAMPER-RTC_P$2") (pintype "bidirectional"))
    )
    (net (code "88") (name "unconnected-(UC1-PD2{slash}TIM3-ETR-PadP$54)") (class "Default")
      (node (ref "UC1") (pin "P$54") (pinfunction "PD2/TIM3-ETR_P$54") (pintype "bidirectional"))
    )
  )
)
